# GZ.net
KiCad netlist of a schematic drawn in Altium Designer
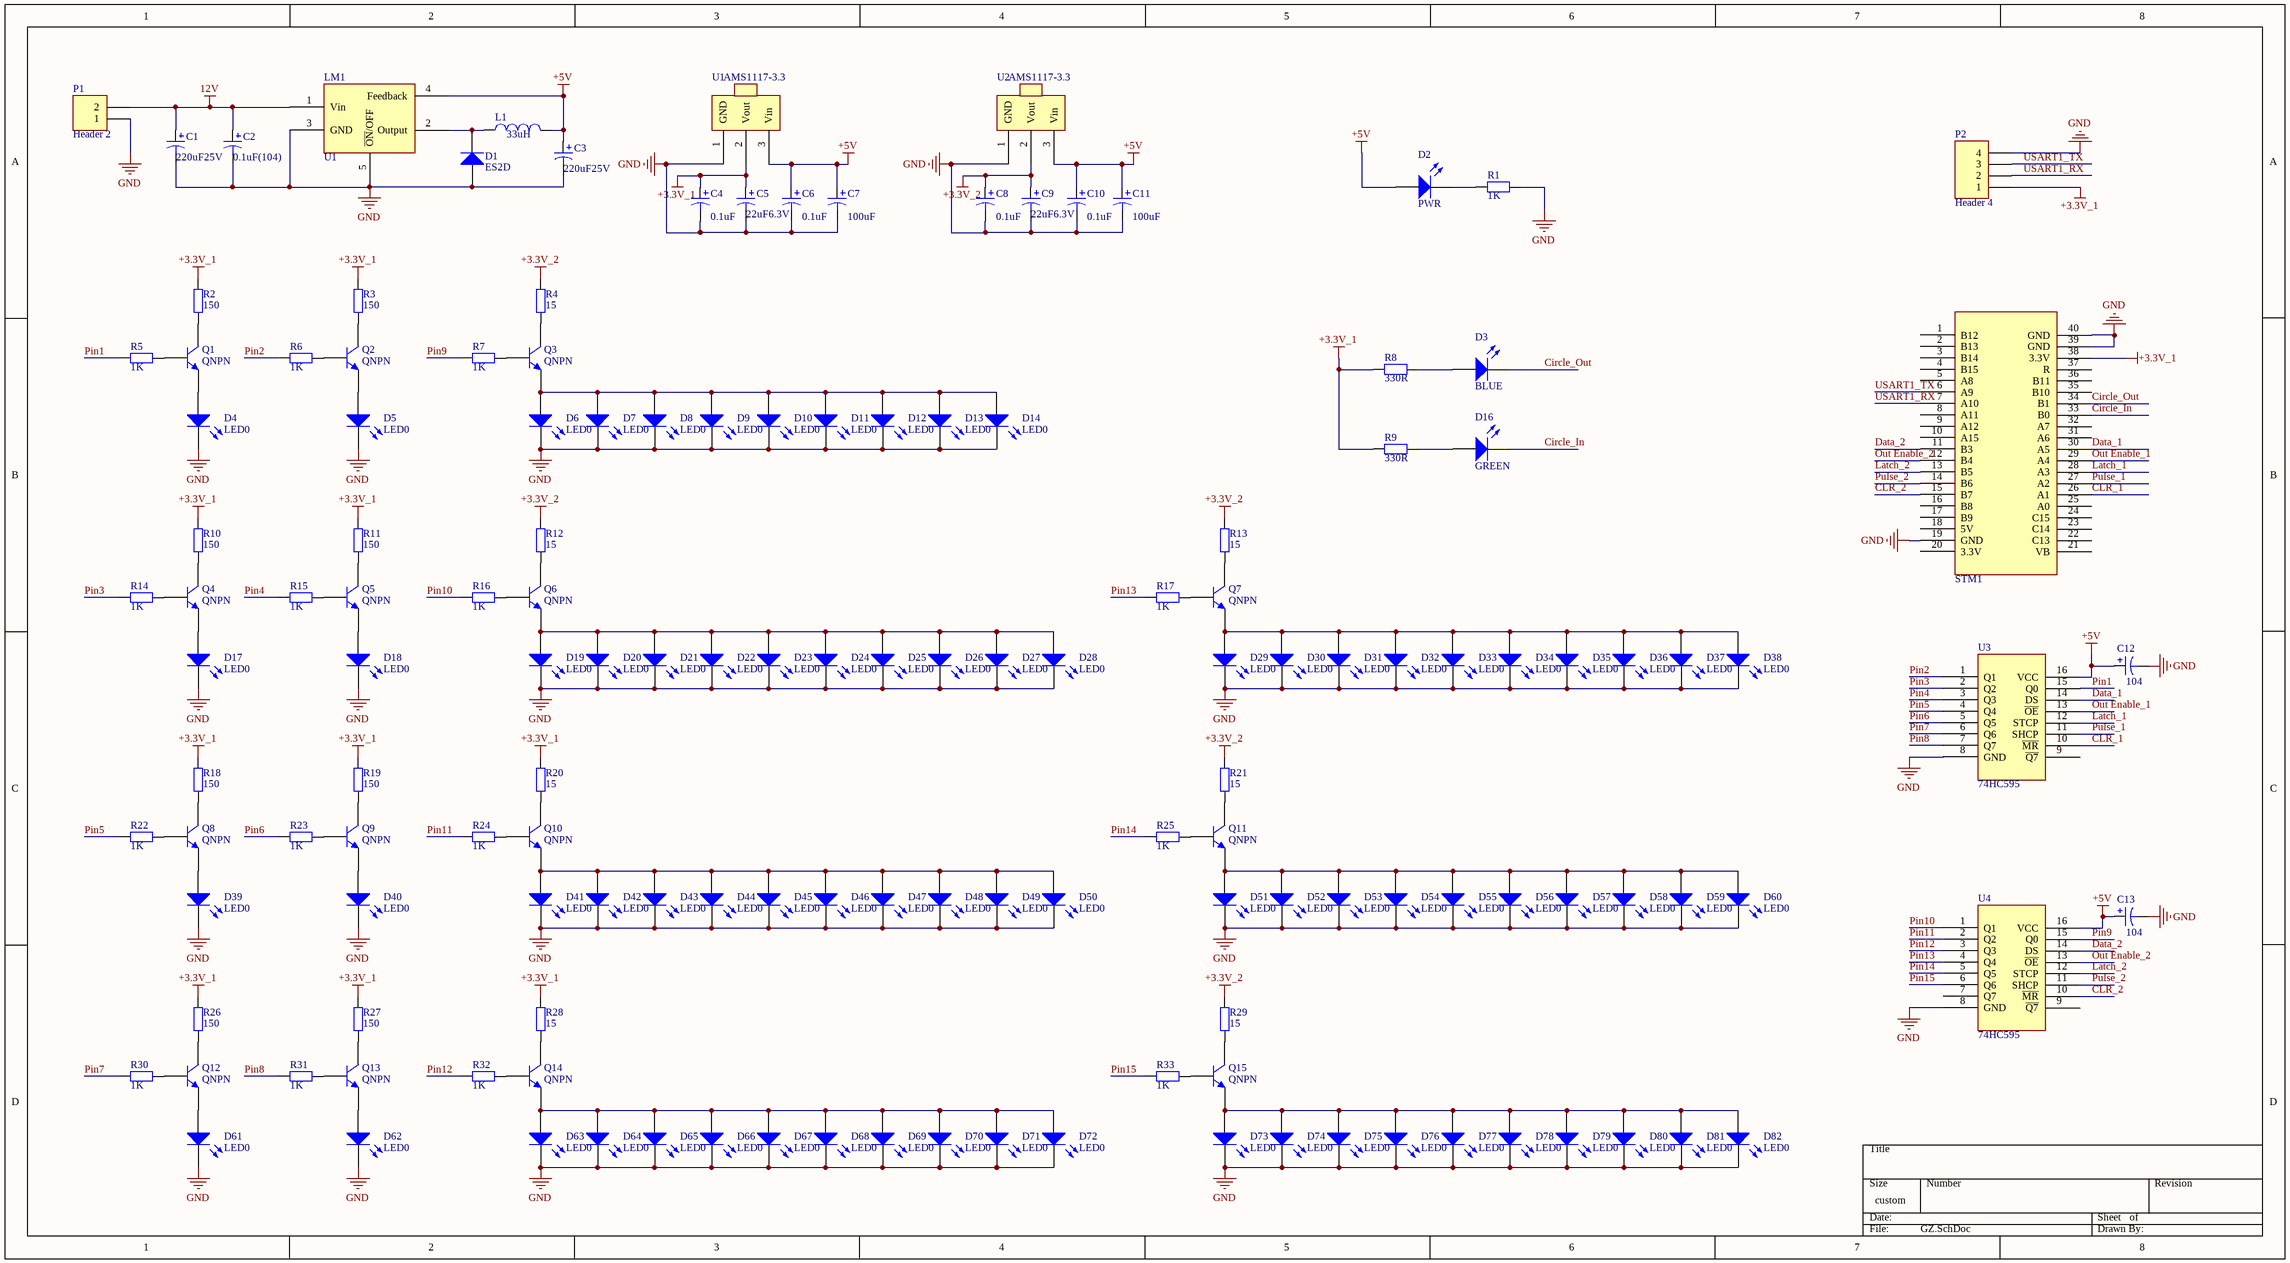
[diagram p0: GZ.SchDoc]

(export (version "E")
  (design (tool "Eeschema 10.0.6"))
  (components
    (comp (ref "C1")
      (value "220uF25V")
      (footprint "3mmcap")
      (description "直插铝电解电容")
      (fields (field (name "PUBLISHER") "Altium Limited"))
      (libsource (lib "Miscellaneous Devices") (part "Cap Pol1"))
    )
    (comp (ref "C2")
      (value "0.1uF(104)")
      (footprint "C0805")
      (description "Polarized Capacitor (Surface Mount)")
      (fields (field (name "PUBLISHER") "Altium Limited"))
      (libsource (lib "Miscellaneous Devices") (part "Cap Pol3"))
    )
    (comp (ref "C3")
      (value "220uF25V")
      (footprint "3mmcap")
      (description "直插铝电解电容")
      (fields (field (name "PUBLISHER") "Altium Limited"))
      (libsource (lib "Miscellaneous Devices") (part "Cap Pol1"))
    )
    (comp (ref "C4")
      (value "0.1uF")
      (footprint "C0805")
      (description "Polarized Capacitor (Surface Mount)")
      (fields (field (name "Comment") "0.1uF(104)") (field (name "PUBLISHER") "Altium Limited"))
      (libsource (lib "Miscellaneous Devices") (part "Cap Pol3"))
    )
    (comp (ref "C5")
      (value "22uF6.3V")
      (footprint "C0805")
      (description "Polarized Capacitor (Surface Mount)")
      (fields (field (name "Comment") "100uf(107)") (field (name "PUBLISHER") "Altium Limited"))
      (libsource (lib "Miscellaneous Devices") (part "Cap Pol3"))
    )
    (comp (ref "C6")
      (value "0.1uF")
      (footprint "C0805")
      (description "Polarized Capacitor (Surface Mount)")
      (fields (field (name "Comment") "0.1uF(104)") (field (name "PUBLISHER") "Altium Limited"))
      (libsource (lib "Miscellaneous Devices") (part "Cap Pol3"))
    )
    (comp (ref "C7")
      (value "100uF")
      (footprint "C0805")
      (description "Polarized Capacitor (Surface Mount)")
      (fields (field (name "Comment") "100uf(107)") (field (name "PUBLISHER") "Altium Limited"))
      (libsource (lib "Miscellaneous Devices") (part "Cap Pol3"))
    )
    (comp (ref "C8")
      (value "0.1uF")
      (footprint "C0805")
      (description "Polarized Capacitor (Surface Mount)")
      (fields (field (name "Comment") "0.1uF(104)") (field (name "PUBLISHER") "Altium Limited"))
      (libsource (lib "Miscellaneous Devices") (part "Cap Pol3"))
    )
    (comp (ref "C9")
      (value "22uF6.3V")
      (footprint "C0805")
      (description "Polarized Capacitor (Surface Mount)")
      (fields (field (name "Comment") "100uf(107)") (field (name "PUBLISHER") "Altium Limited"))
      (libsource (lib "Miscellaneous Devices") (part "Cap Pol3"))
    )
    (comp (ref "C10")
      (value "0.1uF")
      (footprint "C0805")
      (description "Polarized Capacitor (Surface Mount)")
      (fields (field (name "Comment") "0.1uF(104)") (field (name "PUBLISHER") "Altium Limited"))
      (libsource (lib "Miscellaneous Devices") (part "Cap Pol3"))
    )
    (comp (ref "C11")
      (value "100uF")
      (footprint "C0805")
      (description "Polarized Capacitor (Surface Mount)")
      (fields (field (name "Comment") "100uf(107)") (field (name "PUBLISHER") "Altium Limited"))
      (libsource (lib "Miscellaneous Devices") (part "Cap Pol3"))
    )
    (comp (ref "C12")
      (value "104")
      (footprint "C0805")
      (description "Polarized Capacitor (Surface Mount)")
      (fields (field (name "Comment") "0.1uF(104)") (field (name "PUBLISHER") "Altium Limited"))
      (libsource (lib "Miscellaneous Devices") (part "Cap Pol3"))
    )
    (comp (ref "C13")
      (value "104")
      (footprint "C0805")
      (description "Polarized Capacitor (Surface Mount)")
      (fields (field (name "Comment") "0.1uF(104)") (field (name "PUBLISHER") "Altium Limited"))
      (libsource (lib "Miscellaneous Devices") (part "Cap Pol3"))
    )
    (comp (ref "D1")
      (value "ES2D")
      (footprint "SMC")
      (description "Diode")
      (fields (field (name "PUBLISHER") "Altium Limited"))
      (libsource (lib "Miscellaneous Devices") (part "Diode"))
    )
    (comp (ref "D2")
      (value "PWR")
      (footprint "3mm")
      (description "RED-LED")
      (fields (field (name "PUBLISHER") "Altium Limited"))
      (libsource (lib "Miscellaneous Devices") (part "LED0"))
    )
    (comp (ref "D3")
      (value "BLUE")
      (footprint "3mm")
      (description "BLUE-LED")
      (fields (field (name "PUBLISHER") "Altium Limited"))
      (libsource (lib "Miscellaneous Devices") (part "LED0"))
    )
    (comp (ref "D4")
      (value "LED0")
      (footprint "5mm")
      (description "850nm IR-LED")
      (fields (field (name "PUBLISHER") "Altium Limited"))
      (libsource (lib "Miscellaneous Devices") (part "LED0"))
    )
    (comp (ref "D5")
      (value "LED0")
      (footprint "5mm")
      (description "850nm IR-LED")
      (fields (field (name "PUBLISHER") "Altium Limited"))
      (libsource (lib "Miscellaneous Devices") (part "LED0"))
    )
    (comp (ref "D6")
      (value "LED0")
      (footprint "5mm")
      (description "850nm IR-LED")
      (fields (field (name "PUBLISHER") "Altium Limited"))
      (libsource (lib "Miscellaneous Devices") (part "LED0"))
    )
    (comp (ref "D7")
      (value "LED0")
      (footprint "5mm")
      (description "850nm IR-LED")
      (fields (field (name "PUBLISHER") "Altium Limited"))
      (libsource (lib "Miscellaneous Devices") (part "LED0"))
    )
    (comp (ref "D8")
      (value "LED0")
      (footprint "5mm")
      (description "850nm IR-LED")
      (fields (field (name "PUBLISHER") "Altium Limited"))
      (libsource (lib "Miscellaneous Devices") (part "LED0"))
    )
    (comp (ref "D9")
      (value "LED0")
      (footprint "5mm")
      (description "850nm IR-LED")
      (fields (field (name "PUBLISHER") "Altium Limited"))
      (libsource (lib "Miscellaneous Devices") (part "LED0"))
    )
    (comp (ref "D10")
      (value "LED0")
      (footprint "5mm")
      (description "850nm IR-LED")
      (fields (field (name "PUBLISHER") "Altium Limited"))
      (libsource (lib "Miscellaneous Devices") (part "LED0"))
    )
    (comp (ref "D11")
      (value "LED0")
      (footprint "5mm")
      (description "850nm IR-LED")
      (fields (field (name "PUBLISHER") "Altium Limited"))
      (libsource (lib "Miscellaneous Devices") (part "LED0"))
    )
    (comp (ref "D12")
      (value "LED0")
      (footprint "5mm")
      (description "850nm IR-LED")
      (fields (field (name "PUBLISHER") "Altium Limited"))
      (libsource (lib "Miscellaneous Devices") (part "LED0"))
    )
    (comp (ref "D13")
      (value "LED0")
      (footprint "5mm")
      (description "850nm IR-LED")
      (fields (field (name "PUBLISHER") "Altium Limited"))
      (libsource (lib "Miscellaneous Devices") (part "LED0"))
    )
    (comp (ref "D14")
      (value "LED0")
      (footprint "5mm")
      (description "850nm IR-LED")
      (fields (field (name "PUBLISHER") "Altium Limited"))
      (libsource (lib "Miscellaneous Devices") (part "LED0"))
    )
    (comp (ref "D16")
      (value "GREEN")
      (footprint "3mm")
      (description "GREEN-LED")
      (fields (field (name "PUBLISHER") "Altium Limited"))
      (libsource (lib "Miscellaneous Devices") (part "LED0"))
    )
    (comp (ref "D17")
      (value "LED0")
      (footprint "5mm")
      (description "850nm IR-LED")
      (fields (field (name "PUBLISHER") "Altium Limited"))
      (libsource (lib "Miscellaneous Devices") (part "LED0"))
    )
    (comp (ref "D18")
      (value "LED0")
      (footprint "5mm")
      (description "850nm IR-LED")
      (fields (field (name "PUBLISHER") "Altium Limited"))
      (libsource (lib "Miscellaneous Devices") (part "LED0"))
    )
    (comp (ref "D19")
      (value "LED0")
      (footprint "3mm")
      (description "940nm IR-LED")
      (fields (field (name "PUBLISHER") "Altium Limited"))
      (libsource (lib "Miscellaneous Devices") (part "LED0"))
    )
    (comp (ref "D20")
      (value "LED0")
      (footprint "3mm")
      (description "940nm IR-LED")
      (fields (field (name "PUBLISHER") "Altium Limited"))
      (libsource (lib "Miscellaneous Devices") (part "LED0"))
    )
    (comp (ref "D21")
      (value "LED0")
      (footprint "3mm")
      (description "940nm IR-LED")
      (fields (field (name "PUBLISHER") "Altium Limited"))
      (libsource (lib "Miscellaneous Devices") (part "LED0"))
    )
    (comp (ref "D22")
      (value "LED0")
      (footprint "3mm")
      (description "940nm IR-LED")
      (fields (field (name "PUBLISHER") "Altium Limited"))
      (libsource (lib "Miscellaneous Devices") (part "LED0"))
    )
    (comp (ref "D23")
      (value "LED0")
      (footprint "3mm")
      (description "940nm IR-LED")
      (fields (field (name "PUBLISHER") "Altium Limited"))
      (libsource (lib "Miscellaneous Devices") (part "LED0"))
    )
    (comp (ref "D24")
      (value "LED0")
      (footprint "3mm")
      (description "940nm IR-LED")
      (fields (field (name "PUBLISHER") "Altium Limited"))
      (libsource (lib "Miscellaneous Devices") (part "LED0"))
    )
    (comp (ref "D25")
      (value "LED0")
      (footprint "3mm")
      (description "940nm IR-LED")
      (fields (field (name "PUBLISHER") "Altium Limited"))
      (libsource (lib "Miscellaneous Devices") (part "LED0"))
    )
    (comp (ref "D26")
      (value "LED0")
      (footprint "3mm")
      (description "940nm IR-LED")
      (fields (field (name "PUBLISHER") "Altium Limited"))
      (libsource (lib "Miscellaneous Devices") (part "LED0"))
    )
    (comp (ref "D27")
      (value "LED0")
      (footprint "3mm")
      (description "940nm IR-LED")
      (fields (field (name "PUBLISHER") "Altium Limited"))
      (libsource (lib "Miscellaneous Devices") (part "LED0"))
    )
    (comp (ref "D28")
      (value "LED0")
      (footprint "3mm")
      (description "940nm IR-LED")
      (fields (field (name "PUBLISHER") "Altium Limited"))
      (libsource (lib "Miscellaneous Devices") (part "LED0"))
    )
    (comp (ref "D29")
      (value "LED0")
      (footprint "3mm")
      (description "940nm IR-LED")
      (fields (field (name "PUBLISHER") "Altium Limited"))
      (libsource (lib "Miscellaneous Devices") (part "LED0"))
    )
    (comp (ref "D30")
      (value "LED0")
      (footprint "3mm")
      (description "940nm IR-LED")
      (fields (field (name "PUBLISHER") "Altium Limited"))
      (libsource (lib "Miscellaneous Devices") (part "LED0"))
    )
    (comp (ref "D31")
      (value "LED0")
      (footprint "3mm")
      (description "940nm IR-LED")
      (fields (field (name "PUBLISHER") "Altium Limited"))
      (libsource (lib "Miscellaneous Devices") (part "LED0"))
    )
    (comp (ref "D32")
      (value "LED0")
      (footprint "3mm")
      (description "940nm IR-LED")
      (fields (field (name "PUBLISHER") "Altium Limited"))
      (libsource (lib "Miscellaneous Devices") (part "LED0"))
    )
    (comp (ref "D33")
      (value "LED0")
      (footprint "3mm")
      (description "940nm IR-LED")
      (fields (field (name "PUBLISHER") "Altium Limited"))
      (libsource (lib "Miscellaneous Devices") (part "LED0"))
    )
    (comp (ref "D34")
      (value "LED0")
      (footprint "3mm")
      (description "940nm IR-LED")
      (fields (field (name "PUBLISHER") "Altium Limited"))
      (libsource (lib "Miscellaneous Devices") (part "LED0"))
    )
    (comp (ref "D35")
      (value "LED0")
      (footprint "3mm")
      (description "940nm IR-LED")
      (fields (field (name "PUBLISHER") "Altium Limited"))
      (libsource (lib "Miscellaneous Devices") (part "LED0"))
    )
    (comp (ref "D36")
      (value "LED0")
      (footprint "3mm")
      (description "940nm IR-LED")
      (fields (field (name "PUBLISHER") "Altium Limited"))
      (libsource (lib "Miscellaneous Devices") (part "LED0"))
    )
    (comp (ref "D37")
      (value "LED0")
      (footprint "3mm")
      (description "940nm IR-LED")
      (fields (field (name "PUBLISHER") "Altium Limited"))
      (libsource (lib "Miscellaneous Devices") (part "LED0"))
    )
    (comp (ref "D38")
      (value "LED0")
      (footprint "3mm")
      (description "940nm IR-LED")
      (fields (field (name "PUBLISHER") "Altium Limited"))
      (libsource (lib "Miscellaneous Devices") (part "LED0"))
    )
    (comp (ref "D39")
      (value "LED0")
      (footprint "3mm")
      (description "940nm IR-LED")
      (fields (field (name "PUBLISHER") "Altium Limited"))
      (libsource (lib "Miscellaneous Devices") (part "LED0"))
    )
    (comp (ref "D40")
      (value "LED0")
      (footprint "3mm")
      (description "940nm IR-LED")
      (fields (field (name "PUBLISHER") "Altium Limited"))
      (libsource (lib "Miscellaneous Devices") (part "LED0"))
    )
    (comp (ref "D41")
      (value "LED0")
      (footprint "3mm")
      (description "940nm IR-LED")
      (fields (field (name "PUBLISHER") "Altium Limited"))
      (libsource (lib "Miscellaneous Devices") (part "LED0"))
    )
    (comp (ref "D42")
      (value "LED0")
      (footprint "3mm")
      (description "940nm IR-LED")
      (fields (field (name "PUBLISHER") "Altium Limited"))
      (libsource (lib "Miscellaneous Devices") (part "LED0"))
    )
    (comp (ref "D43")
      (value "LED0")
      (footprint "3mm")
      (description "940nm IR-LED")
      (fields (field (name "PUBLISHER") "Altium Limited"))
      (libsource (lib "Miscellaneous Devices") (part "LED0"))
    )
    (comp (ref "D44")
      (value "LED0")
      (footprint "3mm")
      (description "940nm IR-LED")
      (fields (field (name "PUBLISHER") "Altium Limited"))
      (libsource (lib "Miscellaneous Devices") (part "LED0"))
    )
    (comp (ref "D45")
      (value "LED0")
      (footprint "3mm")
      (description "940nm IR-LED")
      (fields (field (name "PUBLISHER") "Altium Limited"))
      (libsource (lib "Miscellaneous Devices") (part "LED0"))
    )
    (comp (ref "D46")
      (value "LED0")
      (footprint "3mm")
      (description "940nm IR-LED")
      (fields (field (name "PUBLISHER") "Altium Limited"))
      (libsource (lib "Miscellaneous Devices") (part "LED0"))
    )
    (comp (ref "D47")
      (value "LED0")
      (footprint "3mm")
      (description "940nm IR-LED")
      (fields (field (name "PUBLISHER") "Altium Limited"))
      (libsource (lib "Miscellaneous Devices") (part "LED0"))
    )
    (comp (ref "D48")
      (value "LED0")
      (footprint "3mm")
      (description "940nm IR-LED")
      (fields (field (name "PUBLISHER") "Altium Limited"))
      (libsource (lib "Miscellaneous Devices") (part "LED0"))
    )
    (comp (ref "D49")
      (value "LED0")
      (footprint "3mm")
      (description "940nm IR-LED")
      (fields (field (name "PUBLISHER") "Altium Limited"))
      (libsource (lib "Miscellaneous Devices") (part "LED0"))
    )
    (comp (ref "D50")
      (value "LED0")
      (footprint "3mm")
      (description "940nm IR-LED")
      (fields (field (name "PUBLISHER") "Altium Limited"))
      (libsource (lib "Miscellaneous Devices") (part "LED0"))
    )
    (comp (ref "D51")
      (value "LED0")
      (footprint "3mm")
      (description "940nm IR-LED")
      (fields (field (name "PUBLISHER") "Altium Limited"))
      (libsource (lib "Miscellaneous Devices") (part "LED0"))
    )
    (comp (ref "D52")
      (value "LED0")
      (footprint "3mm")
      (description "940nm IR-LED")
      (fields (field (name "PUBLISHER") "Altium Limited"))
      (libsource (lib "Miscellaneous Devices") (part "LED0"))
    )
    (comp (ref "D53")
      (value "LED0")
      (footprint "3mm")
      (description "940nm IR-LED")
      (fields (field (name "PUBLISHER") "Altium Limited"))
      (libsource (lib "Miscellaneous Devices") (part "LED0"))
    )
    (comp (ref "D54")
      (value "LED0")
      (footprint "3mm")
      (description "940nm IR-LED")
      (fields (field (name "PUBLISHER") "Altium Limited"))
      (libsource (lib "Miscellaneous Devices") (part "LED0"))
    )
    (comp (ref "D55")
      (value "LED0")
      (footprint "3mm")
      (description "940nm IR-LED")
      (fields (field (name "PUBLISHER") "Altium Limited"))
      (libsource (lib "Miscellaneous Devices") (part "LED0"))
    )
    (comp (ref "D56")
      (value "LED0")
      (footprint "3mm")
      (description "940nm IR-LED")
      (fields (field (name "PUBLISHER") "Altium Limited"))
      (libsource (lib "Miscellaneous Devices") (part "LED0"))
    )
    (comp (ref "D57")
      (value "LED0")
      (footprint "3mm")
      (description "940nm IR-LED")
      (fields (field (name "PUBLISHER") "Altium Limited"))
      (libsource (lib "Miscellaneous Devices") (part "LED0"))
    )
    (comp (ref "D58")
      (value "LED0")
      (footprint "3mm")
      (description "940nm IR-LED")
      (fields (field (name "PUBLISHER") "Altium Limited"))
      (libsource (lib "Miscellaneous Devices") (part "LED0"))
    )
    (comp (ref "D59")
      (value "LED0")
      (footprint "3mm")
      (description "940nm IR-LED")
      (fields (field (name "PUBLISHER") "Altium Limited"))
      (libsource (lib "Miscellaneous Devices") (part "LED0"))
    )
    (comp (ref "D60")
      (value "LED0")
      (footprint "3mm")
      (description "940nm IR-LED")
      (fields (field (name "PUBLISHER") "Altium Limited"))
      (libsource (lib "Miscellaneous Devices") (part "LED0"))
    )
    (comp (ref "D61")
      (value "LED0")
      (footprint "3mm")
      (description "940nm IR-LED")
      (fields (field (name "PUBLISHER") "Altium Limited"))
      (libsource (lib "Miscellaneous Devices") (part "LED0"))
    )
    (comp (ref "D62")
      (value "LED0")
      (footprint "3mm")
      (description "940nm IR-LED")
      (fields (field (name "PUBLISHER") "Altium Limited"))
      (libsource (lib "Miscellaneous Devices") (part "LED0"))
    )
    (comp (ref "D63")
      (value "LED0")
      (footprint "3mm")
      (description "940nm IR-LED")
      (fields (field (name "PUBLISHER") "Altium Limited"))
      (libsource (lib "Miscellaneous Devices") (part "LED0"))
    )
    (comp (ref "D64")
      (value "LED0")
      (footprint "3mm")
      (description "940nm IR-LED")
      (fields (field (name "PUBLISHER") "Altium Limited"))
      (libsource (lib "Miscellaneous Devices") (part "LED0"))
    )
    (comp (ref "D65")
      (value "LED0")
      (footprint "3mm")
      (description "940nm IR-LED")
      (fields (field (name "PUBLISHER") "Altium Limited"))
      (libsource (lib "Miscellaneous Devices") (part "LED0"))
    )
    (comp (ref "D66")
      (value "LED0")
      (footprint "3mm")
      (description "940nm IR-LED")
      (fields (field (name "PUBLISHER") "Altium Limited"))
      (libsource (lib "Miscellaneous Devices") (part "LED0"))
    )
    (comp (ref "D67")
      (value "LED0")
      (footprint "3mm")
      (description "940nm IR-LED")
      (fields (field (name "PUBLISHER") "Altium Limited"))
      (libsource (lib "Miscellaneous Devices") (part "LED0"))
    )
    (comp (ref "D68")
      (value "LED0")
      (footprint "3mm")
      (description "940nm IR-LED")
      (fields (field (name "PUBLISHER") "Altium Limited"))
      (libsource (lib "Miscellaneous Devices") (part "LED0"))
    )
    (comp (ref "D69")
      (value "LED0")
      (footprint "3mm")
      (description "940nm IR-LED")
      (fields (field (name "PUBLISHER") "Altium Limited"))
      (libsource (lib "Miscellaneous Devices") (part "LED0"))
    )
    (comp (ref "D70")
      (value "LED0")
      (footprint "3mm")
      (description "940nm IR-LED")
      (fields (field (name "PUBLISHER") "Altium Limited"))
      (libsource (lib "Miscellaneous Devices") (part "LED0"))
    )
    (comp (ref "D71")
      (value "LED0")
      (footprint "3mm")
      (description "940nm IR-LED")
      (fields (field (name "PUBLISHER") "Altium Limited"))
      (libsource (lib "Miscellaneous Devices") (part "LED0"))
    )
    (comp (ref "D72")
      (value "LED0")
      (footprint "3mm")
      (description "940nm IR-LED")
      (fields (field (name "PUBLISHER") "Altium Limited"))
      (libsource (lib "Miscellaneous Devices") (part "LED0"))
    )
    (comp (ref "D73")
      (value "LED0")
      (footprint "3mm")
      (description "940nm IR-LED")
      (fields (field (name "PUBLISHER") "Altium Limited"))
      (libsource (lib "Miscellaneous Devices") (part "LED0"))
    )
    (comp (ref "D74")
      (value "LED0")
      (footprint "3mm")
      (description "940nm IR-LED")
      (fields (field (name "PUBLISHER") "Altium Limited"))
      (libsource (lib "Miscellaneous Devices") (part "LED0"))
    )
    (comp (ref "D75")
      (value "LED0")
      (footprint "3mm")
      (description "940nm IR-LED")
      (fields (field (name "PUBLISHER") "Altium Limited"))
      (libsource (lib "Miscellaneous Devices") (part "LED0"))
    )
    (comp (ref "D76")
      (value "LED0")
      (footprint "3mm")
      (description "940nm IR-LED")
      (fields (field (name "PUBLISHER") "Altium Limited"))
      (libsource (lib "Miscellaneous Devices") (part "LED0"))
    )
    (comp (ref "D77")
      (value "LED0")
      (footprint "3mm")
      (description "940nm IR-LED")
      (fields (field (name "PUBLISHER") "Altium Limited"))
      (libsource (lib "Miscellaneous Devices") (part "LED0"))
    )
    (comp (ref "D78")
      (value "LED0")
      (footprint "3mm")
      (description "940nm IR-LED")
      (fields (field (name "PUBLISHER") "Altium Limited"))
      (libsource (lib "Miscellaneous Devices") (part "LED0"))
    )
    (comp (ref "D79")
      (value "LED0")
      (footprint "3mm")
      (description "940nm IR-LED")
      (fields (field (name "PUBLISHER") "Altium Limited"))
      (libsource (lib "Miscellaneous Devices") (part "LED0"))
    )
    (comp (ref "D80")
      (value "LED0")
      (footprint "3mm")
      (description "940nm IR-LED")
      (fields (field (name "PUBLISHER") "Altium Limited"))
      (libsource (lib "Miscellaneous Devices") (part "LED0"))
    )
    (comp (ref "D81")
      (value "LED0")
      (footprint "3mm")
      (description "940nm IR-LED")
      (fields (field (name "PUBLISHER") "Altium Limited"))
      (libsource (lib "Miscellaneous Devices") (part "LED0"))
    )
    (comp (ref "D82")
      (value "LED0")
      (footprint "3mm")
      (description "940nm IR-LED")
      (fields (field (name "PUBLISHER") "Altium Limited"))
      (libsource (lib "Miscellaneous Devices") (part "LED0"))
    )
    (comp (ref "L1")
      (value "33uH")
      (footprint "7*7mm贴片电感")
      (fields (field (name "Comment") "Inductor") (field (name "PUBLISHER") "Altium Limited"))
      (libsource (lib "Miscellaneous Devices") (part "Inductor"))
    )
    (comp (ref "LM1")
      (value "U1")
      (footprint "TO-263-5")
      (description "LM2596-5.0")
      (libsource (lib "PPSchlib") (part "LM2596"))
    )
    (comp (ref "P1")
      (value "Header 2")
      (footprint "HDR1X2")
      (description "电源接口")
      (fields (field (name "PUBLISHER") "Altium Limited"))
      (libsource (lib "Miscellaneous Connectors") (part "Header 2"))
    )
    (comp (ref "P2")
      (value "Header 4")
      (footprint "HDR1X4")
      (description "串口接口")
      (fields (field (name "PUBLISHER") "Altium Limited"))
      (libsource (lib "Miscellaneous Connectors") (part "Header 4"))
    )
    (comp (ref "Q1")
      (value "QNPN")
      (footprint "SOT-23B_N")
      (description "NPN Bipolar Transistor")
      (fields (field (name "PUBLISHER") "Altium Limited"))
      (libsource (lib "Miscellaneous Devices") (part "QNPN"))
    )
    (comp (ref "Q2")
      (value "QNPN")
      (footprint "SOT-23B_N")
      (description "NPN Bipolar Transistor")
      (fields (field (name "PUBLISHER") "Altium Limited"))
      (libsource (lib "Miscellaneous Devices") (part "QNPN"))
    )
    (comp (ref "Q3")
      (value "QNPN")
      (footprint "SOT-23B_N")
      (description "NPN Bipolar Transistor")
      (fields (field (name "PUBLISHER") "Altium Limited"))
      (libsource (lib "Miscellaneous Devices") (part "QNPN"))
    )
    (comp (ref "Q4")
      (value "QNPN")
      (footprint "SOT-23B_N")
      (description "NPN Bipolar Transistor")
      (fields (field (name "PUBLISHER") "Altium Limited"))
      (libsource (lib "Miscellaneous Devices") (part "QNPN"))
    )
    (comp (ref "Q5")
      (value "QNPN")
      (footprint "SOT-23B_N")
      (description "NPN Bipolar Transistor")
      (fields (field (name "PUBLISHER") "Altium Limited"))
      (libsource (lib "Miscellaneous Devices") (part "QNPN"))
    )
    (comp (ref "Q6")
      (value "QNPN")
      (footprint "SOT-23B_N")
      (description "NPN Bipolar Transistor")
      (fields (field (name "PUBLISHER") "Altium Limited"))
      (libsource (lib "Miscellaneous Devices") (part "QNPN"))
    )
    (comp (ref "Q7")
      (value "QNPN")
      (footprint "SOT-23B_N")
      (description "NPN Bipolar Transistor")
      (fields (field (name "PUBLISHER") "Altium Limited"))
      (libsource (lib "Miscellaneous Devices") (part "QNPN"))
    )
    (comp (ref "Q8")
      (value "QNPN")
      (footprint "SOT-23B_N")
      (description "NPN Bipolar Transistor")
      (fields (field (name "PUBLISHER") "Altium Limited"))
      (libsource (lib "Miscellaneous Devices") (part "QNPN"))
    )
    (comp (ref "Q9")
      (value "QNPN")
      (footprint "SOT-23B_N")
      (description "NPN Bipolar Transistor")
      (fields (field (name "PUBLISHER") "Altium Limited"))
      (libsource (lib "Miscellaneous Devices") (part "QNPN"))
    )
    (comp (ref "Q10")
      (value "QNPN")
      (footprint "SOT-23B_N")
      (description "NPN Bipolar Transistor")
      (fields (field (name "PUBLISHER") "Altium Limited"))
      (libsource (lib "Miscellaneous Devices") (part "QNPN"))
    )
    (comp (ref "Q11")
      (value "QNPN")
      (footprint "SOT-23B_N")
      (description "NPN Bipolar Transistor")
      (fields (field (name "PUBLISHER") "Altium Limited"))
      (libsource (lib "Miscellaneous Devices") (part "QNPN"))
    )
    (comp (ref "Q12")
      (value "QNPN")
      (footprint "SOT-23B_N")
      (description "NPN Bipolar Transistor")
      (fields (field (name "PUBLISHER") "Altium Limited"))
      (libsource (lib "Miscellaneous Devices") (part "QNPN"))
    )
    (comp (ref "Q13")
      (value "QNPN")
      (footprint "SOT-23B_N")
      (description "NPN Bipolar Transistor")
      (fields (field (name "PUBLISHER") "Altium Limited"))
      (libsource (lib "Miscellaneous Devices") (part "QNPN"))
    )
    (comp (ref "Q14")
      (value "QNPN")
      (footprint "SOT-23B_N")
      (description "NPN Bipolar Transistor")
      (fields (field (name "PUBLISHER") "Altium Limited"))
      (libsource (lib "Miscellaneous Devices") (part "QNPN"))
    )
    (comp (ref "Q15")
      (value "QNPN")
      (footprint "SOT-23B_N")
      (description "NPN Bipolar Transistor")
      (fields (field (name "PUBLISHER") "Altium Limited"))
      (libsource (lib "Miscellaneous Devices") (part "QNPN"))
    )
    (comp (ref "R1")
      (value "1K")
      (footprint "6-0805_N")
      (description "Resistor")
      (fields (field (name "Comment") "Res2") (field (name "PUBLISHER") "Altium Limited"))
      (libsource (lib "") (part "Res2_1"))
    )
    (comp (ref "R2")
      (value "150")
      (footprint "6-0805_N")
      (description "Resistor")
      (fields (field (name "Comment") "Res2") (field (name "PUBLISHER") "Altium Limited"))
      (libsource (lib "Miscellaneous Devices") (part "Res2"))
    )
    (comp (ref "R3")
      (value "150")
      (footprint "6-0805_N")
      (description "Resistor")
      (fields (field (name "Comment") "Res2") (field (name "PUBLISHER") "Altium Limited"))
      (libsource (lib "Miscellaneous Devices") (part "Res2"))
    )
    (comp (ref "R4")
      (value "15")
      (footprint "6-0805_N")
      (description "Resistor")
      (fields (field (name "Comment") "Res2") (field (name "PUBLISHER") "Altium Limited"))
      (libsource (lib "Miscellaneous Devices") (part "Res2"))
    )
    (comp (ref "R5")
      (value "1K")
      (footprint "6-0805_N")
      (description "Resistor")
      (fields (field (name "Comment") "Res2") (field (name "PUBLISHER") "Altium Limited"))
      (libsource (lib "") (part "Res2_1"))
    )
    (comp (ref "R6")
      (value "1K")
      (footprint "6-0805_N")
      (description "Resistor")
      (fields (field (name "Comment") "Res2") (field (name "PUBLISHER") "Altium Limited"))
      (libsource (lib "") (part "Res2_1"))
    )
    (comp (ref "R7")
      (value "1K")
      (footprint "6-0805_N")
      (description "Resistor")
      (fields (field (name "Comment") "Res2") (field (name "PUBLISHER") "Altium Limited"))
      (libsource (lib "") (part "Res2_1"))
    )
    (comp (ref "R8")
      (value "330R")
      (footprint "6-0805_N")
      (description "Resistor")
      (fields (field (name "Comment") "Res2") (field (name "PUBLISHER") "Altium Limited"))
      (libsource (lib "") (part "Res2_1"))
    )
    (comp (ref "R9")
      (value "330R")
      (footprint "6-0805_N")
      (description "Resistor")
      (fields (field (name "Comment") "Res2") (field (name "PUBLISHER") "Altium Limited"))
      (libsource (lib "") (part "Res2_1"))
    )
    (comp (ref "R10")
      (value "150")
      (footprint "6-0805_N")
      (description "Resistor")
      (fields (field (name "Comment") "Res2") (field (name "PUBLISHER") "Altium Limited"))
      (libsource (lib "Miscellaneous Devices") (part "Res2"))
    )
    (comp (ref "R11")
      (value "150")
      (footprint "6-0805_N")
      (description "Resistor")
      (fields (field (name "Comment") "Res2") (field (name "PUBLISHER") "Altium Limited"))
      (libsource (lib "Miscellaneous Devices") (part "Res2"))
    )
    (comp (ref "R12")
      (value "15")
      (footprint "6-0805_N")
      (description "Resistor")
      (fields (field (name "Comment") "Res2") (field (name "PUBLISHER") "Altium Limited"))
      (libsource (lib "Miscellaneous Devices") (part "Res2"))
    )
    (comp (ref "R13")
      (value "15")
      (footprint "6-0805_N")
      (description "Resistor")
      (fields (field (name "Comment") "Res2") (field (name "PUBLISHER") "Altium Limited"))
      (libsource (lib "Miscellaneous Devices") (part "Res2"))
    )
    (comp (ref "R14")
      (value "1K")
      (footprint "6-0805_N")
      (description "Resistor")
      (fields (field (name "Comment") "Res2") (field (name "PUBLISHER") "Altium Limited"))
      (libsource (lib "") (part "Res2_1"))
    )
    (comp (ref "R15")
      (value "1K")
      (footprint "6-0805_N")
      (description "Resistor")
      (fields (field (name "Comment") "Res2") (field (name "PUBLISHER") "Altium Limited"))
      (libsource (lib "") (part "Res2_1"))
    )
    (comp (ref "R16")
      (value "1K")
      (footprint "6-0805_N")
      (description "Resistor")
      (fields (field (name "Comment") "Res2") (field (name "PUBLISHER") "Altium Limited"))
      (libsource (lib "") (part "Res2_1"))
    )
    (comp (ref "R17")
      (value "1K")
      (footprint "6-0805_N")
      (description "Resistor")
      (fields (field (name "Comment") "Res2") (field (name "PUBLISHER") "Altium Limited"))
      (libsource (lib "") (part "Res2_1"))
    )
    (comp (ref "R18")
      (value "150")
      (footprint "6-0805_N")
      (description "Resistor")
      (fields (field (name "Comment") "Res2") (field (name "PUBLISHER") "Altium Limited"))
      (libsource (lib "Miscellaneous Devices") (part "Res2"))
    )
    (comp (ref "R19")
      (value "150")
      (footprint "6-0805_N")
      (description "Resistor")
      (fields (field (name "Comment") "Res2") (field (name "PUBLISHER") "Altium Limited"))
      (libsource (lib "Miscellaneous Devices") (part "Res2"))
    )
    (comp (ref "R20")
      (value "15")
      (footprint "6-0805_N")
      (description "Resistor")
      (fields (field (name "Comment") "Res2") (field (name "PUBLISHER") "Altium Limited"))
      (libsource (lib "Miscellaneous Devices") (part "Res2"))
    )
    (comp (ref "R21")
      (value "15")
      (footprint "6-0805_N")
      (description "Resistor")
      (fields (field (name "Comment") "Res2") (field (name "PUBLISHER") "Altium Limited"))
      (libsource (lib "Miscellaneous Devices") (part "Res2"))
    )
    (comp (ref "R22")
      (value "1K")
      (footprint "6-0805_N")
      (description "Resistor")
      (fields (field (name "Comment") "Res2") (field (name "PUBLISHER") "Altium Limited"))
      (libsource (lib "") (part "Res2_1"))
    )
    (comp (ref "R23")
      (value "1K")
      (footprint "6-0805_N")
      (description "Resistor")
      (fields (field (name "Comment") "Res2") (field (name "PUBLISHER") "Altium Limited"))
      (libsource (lib "") (part "Res2_1"))
    )
    (comp (ref "R24")
      (value "1K")
      (footprint "6-0805_N")
      (description "Resistor")
      (fields (field (name "Comment") "Res2") (field (name "PUBLISHER") "Altium Limited"))
      (libsource (lib "") (part "Res2_1"))
    )
    (comp (ref "R25")
      (value "1K")
      (footprint "6-0805_N")
      (description "Resistor")
      (fields (field (name "Comment") "Res2") (field (name "PUBLISHER") "Altium Limited"))
      (libsource (lib "") (part "Res2_1"))
    )
    (comp (ref "R26")
      (value "150")
      (footprint "6-0805_N")
      (description "Resistor")
      (fields (field (name "Comment") "Res2") (field (name "PUBLISHER") "Altium Limited"))
      (libsource (lib "Miscellaneous Devices") (part "Res2"))
    )
    (comp (ref "R27")
      (value "150")
      (footprint "6-0805_N")
      (description "Resistor")
      (fields (field (name "Comment") "Res2") (field (name "PUBLISHER") "Altium Limited"))
      (libsource (lib "Miscellaneous Devices") (part "Res2"))
    )
    (comp (ref "R28")
      (value "15")
      (footprint "6-0805_N")
      (description "Resistor")
      (fields (field (name "Comment") "Res2") (field (name "PUBLISHER") "Altium Limited"))
      (libsource (lib "Miscellaneous Devices") (part "Res2"))
    )
    (comp (ref "R29")
      (value "15")
      (footprint "6-0805_N")
      (description "Resistor")
      (fields (field (name "Comment") "Res2") (field (name "PUBLISHER") "Altium Limited"))
      (libsource (lib "Miscellaneous Devices") (part "Res2"))
    )
    (comp (ref "R30")
      (value "1K")
      (footprint "6-0805_N")
      (description "Resistor")
      (fields (field (name "Comment") "Res2") (field (name "PUBLISHER") "Altium Limited"))
      (libsource (lib "") (part "Res2_1"))
    )
    (comp (ref "R31")
      (value "1K")
      (footprint "6-0805_N")
      (description "Resistor")
      (fields (field (name "Comment") "Res2") (field (name "PUBLISHER") "Altium Limited"))
      (libsource (lib "") (part "Res2_1"))
    )
    (comp (ref "R32")
      (value "1K")
      (footprint "6-0805_N")
      (description "Resistor")
      (fields (field (name "Comment") "Res2") (field (name "PUBLISHER") "Altium Limited"))
      (libsource (lib "") (part "Res2_1"))
    )
    (comp (ref "R33")
      (value "1K")
      (footprint "6-0805_N")
      (description "Resistor")
      (fields (field (name "Comment") "Res2") (field (name "PUBLISHER") "Altium Limited"))
      (libsource (lib "") (part "Res2_1"))
    )
    (comp (ref "STM1")
      (value "STM32F103C8核心板")
      (footprint "STM32F103C8T6")
      (libsource (lib "PPSchlib") (part "STM32F103C8核心板"))
    )
    (comp (ref "U1")
      (value "AMS1117-3.3")
      (footprint "SOT223_N")
      (libsource (lib "PPSchlib") (part "AMS1117-3.3"))
    )
    (comp (ref "U2")
      (value "AMS1117-3.3")
      (footprint "SOT223_N")
      (libsource (lib "PPSchlib") (part "AMS1117-3.3"))
    )
    (comp (ref "U3") (value "74HC595") (footprint "dip16") (libsource (lib "PPSchlib") (part "74HC595")))
    (comp (ref "U4") (value "74HC595") (footprint "dip16") (libsource (lib "PPSchlib") (part "74HC595")))
  )
  (nets
    (net (code "1") (name "+3.3V_1") (class "Default")
      (node (ref "C4") (pin "1") (pinfunction "1_1") (pintype "passive"))
      (node (ref "C5") (pin "1") (pinfunction "1_1") (pintype "passive"))
      (node (ref "P2") (pin "1") (pinfunction "1_1") (pintype "passive"))
      (node (ref "R10") (pin "1") (pinfunction "1_1") (pintype "passive"))
      (node (ref "R11") (pin "1") (pinfunction "1_1") (pintype "passive"))
      (node (ref "R18") (pin "1") (pinfunction "1_1") (pintype "passive"))
      (node (ref "R19") (pin "1") (pinfunction "1_1") (pintype "passive"))
      (node (ref "R2") (pin "1") (pinfunction "1_1") (pintype "passive"))
      (node (ref "R20") (pin "1") (pinfunction "1_1") (pintype "passive"))
      (node (ref "R26") (pin "1") (pinfunction "1_1") (pintype "passive"))
      (node (ref "R27") (pin "1") (pinfunction "1_1") (pintype "passive"))
      (node (ref "R28") (pin "1") (pinfunction "1_1") (pintype "passive"))
      (node (ref "R3") (pin "1") (pinfunction "1_1") (pintype "passive"))
      (node (ref "R8") (pin "2") (pinfunction "2_2") (pintype "passive"))
      (node (ref "R9") (pin "2") (pinfunction "2_2") (pintype "passive"))
      (node (ref "STM1") (pin "38") (pinfunction "3.3V_38") (pintype "passive"))
      (node (ref "U1") (pin "2") (pinfunction "Vout_2") (pintype "passive"))
    )
    (net (code "2") (name "+3.3V_2") (class "Default")
      (node (ref "C8") (pin "1") (pinfunction "1_1") (pintype "passive"))
      (node (ref "C9") (pin "1") (pinfunction "1_1") (pintype "passive"))
      (node (ref "R12") (pin "1") (pinfunction "1_1") (pintype "passive"))
      (node (ref "R13") (pin "1") (pinfunction "1_1") (pintype "passive"))
      (node (ref "R21") (pin "1") (pinfunction "1_1") (pintype "passive"))
      (node (ref "R29") (pin "1") (pinfunction "1_1") (pintype "passive"))
      (node (ref "R4") (pin "1") (pinfunction "1_1") (pintype "passive"))
      (node (ref "U2") (pin "2") (pinfunction "Vout_2") (pintype "passive"))
    )
    (net (code "3") (name "+5V") (class "Default")
      (node (ref "C10") (pin "1") (pinfunction "1_1") (pintype "passive"))
      (node (ref "C11") (pin "1") (pinfunction "1_1") (pintype "passive"))
      (node (ref "C12") (pin "1") (pinfunction "1_1") (pintype "passive"))
      (node (ref "C13") (pin "1") (pinfunction "1_1") (pintype "passive"))
      (node (ref "C3") (pin "1") (pinfunction "1_1") (pintype "passive"))
      (node (ref "C6") (pin "1") (pinfunction "1_1") (pintype "passive"))
      (node (ref "C7") (pin "1") (pinfunction "1_1") (pintype "passive"))
      (node (ref "D2") (pin "1") (pinfunction "A_1") (pintype "passive"))
      (node (ref "L1") (pin "2") (pinfunction "2_2") (pintype "passive"))
      (node (ref "LM1") (pin "4") (pinfunction "Feedback_4") (pintype "passive"))
      (node (ref "U1") (pin "3") (pinfunction "Vin_3") (pintype "passive"))
      (node (ref "U2") (pin "3") (pinfunction "Vin_3") (pintype "passive"))
      (node (ref "U3") (pin "16") (pinfunction "VCC_16") (pintype "passive"))
      (node (ref "U4") (pin "16") (pinfunction "VCC_16") (pintype "passive"))
    )
    (net (code "4") (name "/CLR_1") (class "Default")
      (node (ref "STM1") (pin "26") (pinfunction "A1_26") (pintype "passive"))
      (node (ref "U3") (pin "10") (pinfunction "~{MR}_10") (pintype "passive"))
    )
    (net (code "5") (name "/CLR_2") (class "Default")
      (node (ref "STM1") (pin "15") (pinfunction "B7_15") (pintype "passive"))
      (node (ref "U4") (pin "10") (pinfunction "~{MR}_10") (pintype "passive"))
    )
    (net (code "6") (name "/Circle_In") (class "Default")
      (node (ref "D16") (pin "2") (pinfunction "K_2") (pintype "passive"))
      (node (ref "STM1") (pin "33") (pinfunction "B0_33") (pintype "passive"))
    )
    (net (code "7") (name "/Circle_Out") (class "Default")
      (node (ref "D3") (pin "2") (pinfunction "K_2") (pintype "passive"))
      (node (ref "STM1") (pin "34") (pinfunction "B1_34") (pintype "passive"))
    )
    (net (code "8") (name "/Data_1") (class "Default")
      (node (ref "STM1") (pin "30") (pinfunction "A5_30") (pintype "passive"))
      (node (ref "U3") (pin "14") (pinfunction "DS_14") (pintype "passive"))
    )
    (net (code "9") (name "/Data_2") (class "Default")
      (node (ref "STM1") (pin "11") (pinfunction "B3_11") (pintype "passive"))
      (node (ref "U4") (pin "14") (pinfunction "DS_14") (pintype "passive"))
    )
    (net (code "10") (name "/Latch_1") (class "Default")
      (node (ref "STM1") (pin "28") (pinfunction "A3_28") (pintype "passive"))
      (node (ref "U3") (pin "12") (pinfunction "STCP_12") (pintype "passive"))
    )
    (net (code "11") (name "/Latch_2") (class "Default")
      (node (ref "STM1") (pin "13") (pinfunction "B5_13") (pintype "passive"))
      (node (ref "U4") (pin "12") (pinfunction "STCP_12") (pintype "passive"))
    )
    (net (code "12") (name "/Out Enable_1") (class "Default")
      (node (ref "STM1") (pin "29") (pinfunction "A4_29") (pintype "passive"))
      (node (ref "U3") (pin "13") (pinfunction "~{OE}_13") (pintype "passive"))
    )
    (net (code "13") (name "/Out Enable_2") (class "Default")
      (node (ref "STM1") (pin "12") (pinfunction "B4_12") (pintype "passive"))
      (node (ref "U4") (pin "13") (pinfunction "~{OE}_13") (pintype "passive"))
    )
    (net (code "14") (name "/Pin1") (class "Default")
      (node (ref "R5") (pin "2") (pinfunction "2_2") (pintype "passive"))
      (node (ref "U3") (pin "15") (pinfunction "Q0_15") (pintype "passive"))
    )
    (net (code "15") (name "/Pin2") (class "Default")
      (node (ref "R6") (pin "2") (pinfunction "2_2") (pintype "passive"))
      (node (ref "U3") (pin "1") (pinfunction "Q1_1") (pintype "passive"))
    )
    (net (code "16") (name "/Pin3") (class "Default")
      (node (ref "R14") (pin "2") (pinfunction "2_2") (pintype "passive"))
      (node (ref "U3") (pin "2") (pinfunction "Q2_2") (pintype "passive"))
    )
    (net (code "17") (name "/Pin4") (class "Default")
      (node (ref "R15") (pin "2") (pinfunction "2_2") (pintype "passive"))
      (node (ref "U3") (pin "3") (pinfunction "Q3_3") (pintype "passive"))
    )
    (net (code "18") (name "/Pin5") (class "Default")
      (node (ref "R22") (pin "2") (pinfunction "2_2") (pintype "passive"))
      (node (ref "U3") (pin "4") (pinfunction "Q4_4") (pintype "passive"))
    )
    (net (code "19") (name "/Pin6") (class "Default")
      (node (ref "R23") (pin "2") (pinfunction "2_2") (pintype "passive"))
      (node (ref "U3") (pin "5") (pinfunction "Q5_5") (pintype "passive"))
    )
    (net (code "20") (name "/Pin7") (class "Default")
      (node (ref "R30") (pin "2") (pinfunction "2_2") (pintype "passive"))
      (node (ref "U3") (pin "6") (pinfunction "Q6_6") (pintype "passive"))
    )
    (net (code "21") (name "/Pin8") (class "Default")
      (node (ref "R31") (pin "2") (pinfunction "2_2") (pintype "passive"))
      (node (ref "U3") (pin "7") (pinfunction "Q7_7") (pintype "passive"))
    )
    (net (code "22") (name "/Pin9") (class "Default")
      (node (ref "R7") (pin "2") (pinfunction "2_2") (pintype "passive"))
      (node (ref "U4") (pin "15") (pinfunction "Q0_15") (pintype "passive"))
    )
    (net (code "23") (name "/Pin10") (class "Default")
      (node (ref "R16") (pin "2") (pinfunction "2_2") (pintype "passive"))
      (node (ref "U4") (pin "1") (pinfunction "Q1_1") (pintype "passive"))
    )
    (net (code "24") (name "/Pin11") (class "Default")
      (node (ref "R24") (pin "2") (pinfunction "2_2") (pintype "passive"))
      (node (ref "U4") (pin "2") (pinfunction "Q2_2") (pintype "passive"))
    )
    (net (code "25") (name "/Pin12") (class "Default")
      (node (ref "R32") (pin "2") (pinfunction "2_2") (pintype "passive"))
      (node (ref "U4") (pin "3") (pinfunction "Q3_3") (pintype "passive"))
    )
    (net (code "26") (name "/Pin13") (class "Default")
      (node (ref "R17") (pin "2") (pinfunction "2_2") (pintype "passive"))
      (node (ref "U4") (pin "4") (pinfunction "Q4_4") (pintype "passive"))
    )
    (net (code "27") (name "/Pin14") (class "Default")
      (node (ref "R25") (pin "2") (pinfunction "2_2") (pintype "passive"))
      (node (ref "U4") (pin "5") (pinfunction "Q5_5") (pintype "passive"))
    )
    (net (code "28") (name "/Pin15") (class "Default")
      (node (ref "R33") (pin "2") (pinfunction "2_2") (pintype "passive"))
      (node (ref "U4") (pin "6") (pinfunction "Q6_6") (pintype "passive"))
    )
    (net (code "29") (name "/Pulse_1") (class "Default")
      (node (ref "STM1") (pin "27") (pinfunction "A2_27") (pintype "passive"))
      (node (ref "U3") (pin "11") (pinfunction "SHCP_11") (pintype "passive"))
    )
    (net (code "30") (name "/Pulse_2") (class "Default")
      (node (ref "STM1") (pin "14") (pinfunction "B6_14") (pintype "passive"))
      (node (ref "U4") (pin "11") (pinfunction "SHCP_11") (pintype "passive"))
    )
    (net (code "31") (name "/USART1_RX") (class "Default")
      (node (ref "P2") (pin "2") (pinfunction "2_2") (pintype "passive"))
      (node (ref "STM1") (pin "7") (pinfunction "A10_7") (pintype "passive"))
    )
    (net (code "32") (name "/USART1_TX") (class "Default")
      (node (ref "P2") (pin "3") (pinfunction "3_3") (pintype "passive"))
      (node (ref "STM1") (pin "6") (pinfunction "A9_6") (pintype "passive"))
    )
    (net (code "33") (name "12V") (class "Default")
      (node (ref "C1") (pin "1") (pinfunction "1_1") (pintype "passive"))
      (node (ref "C2") (pin "1") (pinfunction "1_1") (pintype "passive"))
      (node (ref "LM1") (pin "1") (pinfunction "Vin_1") (pintype "passive"))
      (node (ref "P1") (pin "2") (pinfunction "2_2") (pintype "passive"))
    )
    (net (code "34") (name "GND") (class "Default")
      (node (ref "C1") (pin "2") (pinfunction "2_2") (pintype "passive"))
      (node (ref "C10") (pin "2") (pinfunction "2_2") (pintype "passive"))
      (node (ref "C11") (pin "2") (pinfunction "2_2") (pintype "passive"))
      (node (ref "C12") (pin "2") (pinfunction "2_2") (pintype "passive"))
      (node (ref "C13") (pin "2") (pinfunction "2_2") (pintype "passive"))
      (node (ref "C2") (pin "2") (pinfunction "2_2") (pintype "passive"))
      (node (ref "C3") (pin "2") (pinfunction "2_2") (pintype "passive"))
      (node (ref "C4") (pin "2") (pinfunction "2_2") (pintype "passive"))
      (node (ref "C5") (pin "2") (pinfunction "2_2") (pintype "passive"))
      (node (ref "C6") (pin "2") (pinfunction "2_2") (pintype "passive"))
      (node (ref "C7") (pin "2") (pinfunction "2_2") (pintype "passive"))
      (node (ref "C8") (pin "2") (pinfunction "2_2") (pintype "passive"))
      (node (ref "C9") (pin "2") (pinfunction "2_2") (pintype "passive"))
      (node (ref "D1") (pin "1") (pinfunction "A_1") (pintype "passive"))
      (node (ref "D10") (pin "2") (pinfunction "K_2") (pintype "passive"))
      (node (ref "D11") (pin "2") (pinfunction "K_2") (pintype "passive"))
      (node (ref "D12") (pin "2") (pinfunction "K_2") (pintype "passive"))
      (node (ref "D13") (pin "2") (pinfunction "K_2") (pintype "passive"))
      (node (ref "D14") (pin "2") (pinfunction "K_2") (pintype "passive"))
      (node (ref "D17") (pin "2") (pinfunction "K_2") (pintype "passive"))
      (node (ref "D18") (pin "2") (pinfunction "K_2") (pintype "passive"))
      (node (ref "D19") (pin "2") (pinfunction "K_2") (pintype "passive"))
      (node (ref "D20") (pin "2") (pinfunction "K_2") (pintype "passive"))
      (node (ref "D21") (pin "2") (pinfunction "K_2") (pintype "passive"))
      (node (ref "D22") (pin "2") (pinfunction "K_2") (pintype "passive"))
      (node (ref "D23") (pin "2") (pinfunction "K_2") (pintype "passive"))
      (node (ref "D24") (pin "2") (pinfunction "K_2") (pintype "passive"))
      (node (ref "D25") (pin "2") (pinfunction "K_2") (pintype "passive"))
      (node (ref "D26") (pin "2") (pinfunction "K_2") (pintype "passive"))
      (node (ref "D27") (pin "2") (pinfunction "K_2") (pintype "passive"))
      (node (ref "D28") (pin "2") (pinfunction "K_2") (pintype "passive"))
      (node (ref "D29") (pin "2") (pinfunction "K_2") (pintype "passive"))
      (node (ref "D30") (pin "2") (pinfunction "K_2") (pintype "passive"))
      (node (ref "D31") (pin "2") (pinfunction "K_2") (pintype "passive"))
      (node (ref "D32") (pin "2") (pinfunction "K_2") (pintype "passive"))
      (node (ref "D33") (pin "2") (pinfunction "K_2") (pintype "passive"))
      (node (ref "D34") (pin "2") (pinfunction "K_2") (pintype "passive"))
      (node (ref "D35") (pin "2") (pinfunction "K_2") (pintype "passive"))
      (node (ref "D36") (pin "2") (pinfunction "K_2") (pintype "passive"))
      (node (ref "D37") (pin "2") (pinfunction "K_2") (pintype "passive"))
      (node (ref "D38") (pin "2") (pinfunction "K_2") (pintype "passive"))
      (node (ref "D39") (pin "2") (pinfunction "K_2") (pintype "passive"))
      (node (ref "D4") (pin "2") (pinfunction "K_2") (pintype "passive"))
      (node (ref "D40") (pin "2") (pinfunction "K_2") (pintype "passive"))
      (node (ref "D41") (pin "2") (pinfunction "K_2") (pintype "passive"))
      (node (ref "D42") (pin "2") (pinfunction "K_2") (pintype "passive"))
      (node (ref "D43") (pin "2") (pinfunction "K_2") (pintype "passive"))
      (node (ref "D44") (pin "2") (pinfunction "K_2") (pintype "passive"))
      (node (ref "D45") (pin "2") (pinfunction "K_2") (pintype "passive"))
      (node (ref "D46") (pin "2") (pinfunction "K_2") (pintype "passive"))
      (node (ref "D47") (pin "2") (pinfunction "K_2") (pintype "passive"))
      (node (ref "D48") (pin "2") (pinfunction "K_2") (pintype "passive"))
      (node (ref "D49") (pin "2") (pinfunction "K_2") (pintype "passive"))
      (node (ref "D5") (pin "2") (pinfunction "K_2") (pintype "passive"))
      (node (ref "D50") (pin "2") (pinfunction "K_2") (pintype "passive"))
      (node (ref "D51") (pin "2") (pinfunction "K_2") (pintype "passive"))
      (node (ref "D52") (pin "2") (pinfunction "K_2") (pintype "passive"))
      (node (ref "D53") (pin "2") (pinfunction "K_2") (pintype "passive"))
      (node (ref "D54") (pin "2") (pinfunction "K_2") (pintype "passive"))
      (node (ref "D55") (pin "2") (pinfunction "K_2") (pintype "passive"))
      (node (ref "D56") (pin "2") (pinfunction "K_2") (pintype "passive"))
      (node (ref "D57") (pin "2") (pinfunction "K_2") (pintype "passive"))
      (node (ref "D58") (pin "2") (pinfunction "K_2") (pintype "passive"))
      (node (ref "D59") (pin "2") (pinfunction "K_2") (pintype "passive"))
      (node (ref "D6") (pin "2") (pinfunction "K_2") (pintype "passive"))
      (node (ref "D60") (pin "2") (pinfunction "K_2") (pintype "passive"))
      (node (ref "D61") (pin "2") (pinfunction "K_2") (pintype "passive"))
      (node (ref "D62") (pin "2") (pinfunction "K_2") (pintype "passive"))
      (node (ref "D63") (pin "2") (pinfunction "K_2") (pintype "passive"))
      (node (ref "D64") (pin "2") (pinfunction "K_2") (pintype "passive"))
      (node (ref "D65") (pin "2") (pinfunction "K_2") (pintype "passive"))
      (node (ref "D66") (pin "2") (pinfunction "K_2") (pintype "passive"))
      (node (ref "D67") (pin "2") (pinfunction "K_2") (pintype "passive"))
      (node (ref "D68") (pin "2") (pinfunction "K_2") (pintype "passive"))
      (node (ref "D69") (pin "2") (pinfunction "K_2") (pintype "passive"))
      (node (ref "D7") (pin "2") (pinfunction "K_2") (pintype "passive"))
      (node (ref "D70") (pin "2") (pinfunction "K_2") (pintype "passive"))
      (node (ref "D71") (pin "2") (pinfunction "K_2") (pintype "passive"))
      (node (ref "D72") (pin "2") (pinfunction "K_2") (pintype "passive"))
      (node (ref "D73") (pin "2") (pinfunction "K_2") (pintype "passive"))
      (node (ref "D74") (pin "2") (pinfunction "K_2") (pintype "passive"))
      (node (ref "D75") (pin "2") (pinfunction "K_2") (pintype "passive"))
      (node (ref "D76") (pin "2") (pinfunction "K_2") (pintype "passive"))
      (node (ref "D77") (pin "2") (pinfunction "K_2") (pintype "passive"))
      (node (ref "D78") (pin "2") (pinfunction "K_2") (pintype "passive"))
      (node (ref "D79") (pin "2") (pinfunction "K_2") (pintype "passive"))
      (node (ref "D8") (pin "2") (pinfunction "K_2") (pintype "passive"))
      (node (ref "D80") (pin "2") (pinfunction "K_2") (pintype "passive"))
      (node (ref "D81") (pin "2") (pinfunction "K_2") (pintype "passive"))
      (node (ref "D82") (pin "2") (pinfunction "K_2") (pintype "passive"))
      (node (ref "D9") (pin "2") (pinfunction "K_2") (pintype "passive"))
      (node (ref "LM1") (pin "3") (pinfunction "GND_3") (pintype "passive"))
      (node (ref "LM1") (pin "5") (pinfunction "~{ON}/OFF_5") (pintype "passive"))
      (node (ref "P1") (pin "1") (pinfunction "1_1") (pintype "passive"))
      (node (ref "P2") (pin "4") (pinfunction "4_4") (pintype "passive"))
      (node (ref "R1") (pin "1") (pinfunction "1_1") (pintype "passive"))
      (node (ref "STM1") (pin "19") (pinfunction "GND_19") (pintype "passive"))
      (node (ref "STM1") (pin "39") (pinfunction "GND_39") (pintype "passive"))
      (node (ref "STM1") (pin "40") (pinfunction "GND_40") (pintype "passive"))
      (node (ref "U1") (pin "1") (pinfunction "GND_1") (pintype "passive"))
      (node (ref "U2") (pin "1") (pinfunction "GND_1") (pintype "passive"))
      (node (ref "U3") (pin "8") (pinfunction "GND_8") (pintype "passive"))
      (node (ref "U4") (pin "8") (pinfunction "GND_8") (pintype "passive"))
    )
    (net (code "35") (name "Net-(D1-K)") (class "Default")
      (node (ref "D1") (pin "2") (pinfunction "K_2") (pintype "passive"))
      (node (ref "L1") (pin "1") (pinfunction "1_1") (pintype "passive"))
      (node (ref "LM1") (pin "2") (pinfunction "Output_2") (pintype "passive"))
    )
    (net (code "36") (name "Net-(D2-K)") (class "Default")
      (node (ref "D2") (pin "2") (pinfunction "K_2") (pintype "passive"))
      (node (ref "R1") (pin "2") (pinfunction "2_2") (pintype "passive"))
    )
    (net (code "37") (name "Net-(D3-A)") (class "Default")
      (node (ref "D3") (pin "1") (pinfunction "A_1") (pintype "passive"))
      (node (ref "R8") (pin "1") (pinfunction "1_1") (pintype "passive"))
    )
    (net (code "38") (name "Net-(D4-A)") (class "Default")
      (node (ref "D4") (pin "1") (pinfunction "A_1") (pintype "passive"))
      (node (ref "Q1") (pin "2") (pinfunction "E_2") (pintype "passive"))
    )
    (net (code "39") (name "Net-(D5-A)") (class "Default")
      (node (ref "D5") (pin "1") (pinfunction "A_1") (pintype "passive"))
      (node (ref "Q2") (pin "2") (pinfunction "E_2") (pintype "passive"))
    )
    (net (code "40") (name "Net-(D10-A)") (class "Default")
      (node (ref "D10") (pin "1") (pinfunction "A_1") (pintype "passive"))
      (node (ref "D11") (pin "1") (pinfunction "A_1") (pintype "passive"))
      (node (ref "D12") (pin "1") (pinfunction "A_1") (pintype "passive"))
      (node (ref "D13") (pin "1") (pinfunction "A_1") (pintype "passive"))
      (node (ref "D14") (pin "1") (pinfunction "A_1") (pintype "passive"))
      (node (ref "D6") (pin "1") (pinfunction "A_1") (pintype "passive"))
      (node (ref "D7") (pin "1") (pinfunction "A_1") (pintype "passive"))
      (node (ref "D8") (pin "1") (pinfunction "A_1") (pintype "passive"))
      (node (ref "D9") (pin "1") (pinfunction "A_1") (pintype "passive"))
      (node (ref "Q3") (pin "2") (pinfunction "E_2") (pintype "passive"))
    )
    (net (code "41") (name "Net-(D16-A)") (class "Default")
      (node (ref "D16") (pin "1") (pinfunction "A_1") (pintype "passive"))
      (node (ref "R9") (pin "1") (pinfunction "1_1") (pintype "passive"))
    )
    (net (code "42") (name "Net-(D17-A)") (class "Default")
      (node (ref "D17") (pin "1") (pinfunction "A_1") (pintype "passive"))
      (node (ref "Q4") (pin "2") (pinfunction "E_2") (pintype "passive"))
    )
    (net (code "43") (name "Net-(D18-A)") (class "Default")
      (node (ref "D18") (pin "1") (pinfunction "A_1") (pintype "passive"))
      (node (ref "Q5") (pin "2") (pinfunction "E_2") (pintype "passive"))
    )
    (net (code "44") (name "Net-(D19-A)") (class "Default")
      (node (ref "D19") (pin "1") (pinfunction "A_1") (pintype "passive"))
      (node (ref "D20") (pin "1") (pinfunction "A_1") (pintype "passive"))
      (node (ref "D21") (pin "1") (pinfunction "A_1") (pintype "passive"))
      (node (ref "D22") (pin "1") (pinfunction "A_1") (pintype "passive"))
      (node (ref "D23") (pin "1") (pinfunction "A_1") (pintype "passive"))
      (node (ref "D24") (pin "1") (pinfunction "A_1") (pintype "passive"))
      (node (ref "D25") (pin "1") (pinfunction "A_1") (pintype "passive"))
      (node (ref "D26") (pin "1") (pinfunction "A_1") (pintype "passive"))
      (node (ref "D27") (pin "1") (pinfunction "A_1") (pintype "passive"))
      (node (ref "D28") (pin "1") (pinfunction "A_1") (pintype "passive"))
      (node (ref "Q6") (pin "2") (pinfunction "E_2") (pintype "passive"))
    )
    (net (code "45") (name "Net-(D29-A)") (class "Default")
      (node (ref "D29") (pin "1") (pinfunction "A_1") (pintype "passive"))
      (node (ref "D30") (pin "1") (pinfunction "A_1") (pintype "passive"))
      (node (ref "D31") (pin "1") (pinfunction "A_1") (pintype "passive"))
      (node (ref "D32") (pin "1") (pinfunction "A_1") (pintype "passive"))
      (node (ref "D33") (pin "1") (pinfunction "A_1") (pintype "passive"))
      (node (ref "D34") (pin "1") (pinfunction "A_1") (pintype "passive"))
      (node (ref "D35") (pin "1") (pinfunction "A_1") (pintype "passive"))
      (node (ref "D36") (pin "1") (pinfunction "A_1") (pintype "passive"))
      (node (ref "D37") (pin "1") (pinfunction "A_1") (pintype "passive"))
      (node (ref "D38") (pin "1") (pinfunction "A_1") (pintype "passive"))
      (node (ref "Q7") (pin "2") (pinfunction "E_2") (pintype "passive"))
    )
    (net (code "46") (name "Net-(D39-A)") (class "Default")
      (node (ref "D39") (pin "1") (pinfunction "A_1") (pintype "passive"))
      (node (ref "Q8") (pin "2") (pinfunction "E_2") (pintype "passive"))
    )
    (net (code "47") (name "Net-(D40-A)") (class "Default")
      (node (ref "D40") (pin "1") (pinfunction "A_1") (pintype "passive"))
      (node (ref "Q9") (pin "2") (pinfunction "E_2") (pintype "passive"))
    )
    (net (code "48") (name "Net-(D41-A)") (class "Default")
      (node (ref "D41") (pin "1") (pinfunction "A_1") (pintype "passive"))
      (node (ref "D42") (pin "1") (pinfunction "A_1") (pintype "passive"))
      (node (ref "D43") (pin "1") (pinfunction "A_1") (pintype "passive"))
      (node (ref "D44") (pin "1") (pinfunction "A_1") (pintype "passive"))
      (node (ref "D45") (pin "1") (pinfunction "A_1") (pintype "passive"))
      (node (ref "D46") (pin "1") (pinfunction "A_1") (pintype "passive"))
      (node (ref "D47") (pin "1") (pinfunction "A_1") (pintype "passive"))
      (node (ref "D48") (pin "1") (pinfunction "A_1") (pintype "passive"))
      (node (ref "D49") (pin "1") (pinfunction "A_1") (pintype "passive"))
      (node (ref "D50") (pin "1") (pinfunction "A_1") (pintype "passive"))
      (node (ref "Q10") (pin "2") (pinfunction "E_2") (pintype "passive"))
    )
    (net (code "49") (name "Net-(D51-A)") (class "Default")
      (node (ref "D51") (pin "1") (pinfunction "A_1") (pintype "passive"))
      (node (ref "D52") (pin "1") (pinfunction "A_1") (pintype "passive"))
      (node (ref "D53") (pin "1") (pinfunction "A_1") (pintype "passive"))
      (node (ref "D54") (pin "1") (pinfunction "A_1") (pintype "passive"))
      (node (ref "D55") (pin "1") (pinfunction "A_1") (pintype "passive"))
      (node (ref "D56") (pin "1") (pinfunction "A_1") (pintype "passive"))
      (node (ref "D57") (pin "1") (pinfunction "A_1") (pintype "passive"))
      (node (ref "D58") (pin "1") (pinfunction "A_1") (pintype "passive"))
      (node (ref "D59") (pin "1") (pinfunction "A_1") (pintype "passive"))
      (node (ref "D60") (pin "1") (pinfunction "A_1") (pintype "passive"))
      (node (ref "Q11") (pin "2") (pinfunction "E_2") (pintype "passive"))
    )
    (net (code "50") (name "Net-(D61-A)") (class "Default")
      (node (ref "D61") (pin "1") (pinfunction "A_1") (pintype "passive"))
      (node (ref "Q12") (pin "2") (pinfunction "E_2") (pintype "passive"))
    )
    (net (code "51") (name "Net-(D62-A)") (class "Default")
      (node (ref "D62") (pin "1") (pinfunction "A_1") (pintype "passive"))
      (node (ref "Q13") (pin "2") (pinfunction "E_2") (pintype "passive"))
    )
    (net (code "52") (name "Net-(D63-A)") (class "Default")
      (node (ref "D63") (pin "1") (pinfunction "A_1") (pintype "passive"))
      (node (ref "D64") (pin "1") (pinfunction "A_1") (pintype "passive"))
      (node (ref "D65") (pin "1") (pinfunction "A_1") (pintype "passive"))
      (node (ref "D66") (pin "1") (pinfunction "A_1") (pintype "passive"))
      (node (ref "D67") (pin "1") (pinfunction "A_1") (pintype "passive"))
      (node (ref "D68") (pin "1") (pinfunction "A_1") (pintype "passive"))
      (node (ref "D69") (pin "1") (pinfunction "A_1") (pintype "passive"))
      (node (ref "D70") (pin "1") (pinfunction "A_1") (pintype "passive"))
      (node (ref "D71") (pin "1") (pinfunction "A_1") (pintype "passive"))
      (node (ref "D72") (pin "1") (pinfunction "A_1") (pintype "passive"))
      (node (ref "Q14") (pin "2") (pinfunction "E_2") (pintype "passive"))
    )
    (net (code "53") (name "Net-(D73-A)") (class "Default")
      (node (ref "D73") (pin "1") (pinfunction "A_1") (pintype "passive"))
      (node (ref "D74") (pin "1") (pinfunction "A_1") (pintype "passive"))
      (node (ref "D75") (pin "1") (pinfunction "A_1") (pintype "passive"))
      (node (ref "D76") (pin "1") (pinfunction "A_1") (pintype "passive"))
      (node (ref "D77") (pin "1") (pinfunction "A_1") (pintype "passive"))
      (node (ref "D78") (pin "1") (pinfunction "A_1") (pintype "passive"))
      (node (ref "D79") (pin "1") (pinfunction "A_1") (pintype "passive"))
      (node (ref "D80") (pin "1") (pinfunction "A_1") (pintype "passive"))
      (node (ref "D81") (pin "1") (pinfunction "A_1") (pintype "passive"))
      (node (ref "D82") (pin "1") (pinfunction "A_1") (pintype "passive"))
      (node (ref "Q15") (pin "2") (pinfunction "E_2") (pintype "passive"))
    )
    (net (code "54") (name "Net-(Q1-B)") (class "Default")
      (node (ref "Q1") (pin "1") (pinfunction "B_1") (pintype "passive"))
      (node (ref "R5") (pin "1") (pinfunction "1_1") (pintype "passive"))
    )
    (net (code "55") (name "Net-(Q1-C)") (class "Default")
      (node (ref "Q1") (pin "3") (pinfunction "C_3") (pintype "passive"))
      (node (ref "R2") (pin "2") (pinfunction "2_2") (pintype "passive"))
    )
    (net (code "56") (name "Net-(Q2-B)") (class "Default")
      (node (ref "Q2") (pin "1") (pinfunction "B_1") (pintype "passive"))
      (node (ref "R6") (pin "1") (pinfunction "1_1") (pintype "passive"))
    )
    (net (code "57") (name "Net-(Q2-C)") (class "Default")
      (node (ref "Q2") (pin "3") (pinfunction "C_3") (pintype "passive"))
      (node (ref "R3") (pin "2") (pinfunction "2_2") (pintype "passive"))
    )
    (net (code "58") (name "Net-(Q3-B)") (class "Default")
      (node (ref "Q3") (pin "1") (pinfunction "B_1") (pintype "passive"))
      (node (ref "R7") (pin "1") (pinfunction "1_1") (pintype "passive"))
    )
    (net (code "59") (name "Net-(Q3-C)") (class "Default")
      (node (ref "Q3") (pin "3") (pinfunction "C_3") (pintype "passive"))
      (node (ref "R4") (pin "2") (pinfunction "2_2") (pintype "passive"))
    )
    (net (code "60") (name "Net-(Q4-B)") (class "Default")
      (node (ref "Q4") (pin "1") (pinfunction "B_1") (pintype "passive"))
      (node (ref "R14") (pin "1") (pinfunction "1_1") (pintype "passive"))
    )
    (net (code "61") (name "Net-(Q4-C)") (class "Default")
      (node (ref "Q4") (pin "3") (pinfunction "C_3") (pintype "passive"))
      (node (ref "R10") (pin "2") (pinfunction "2_2") (pintype "passive"))
    )
    (net (code "62") (name "Net-(Q5-B)") (class "Default")
      (node (ref "Q5") (pin "1") (pinfunction "B_1") (pintype "passive"))
      (node (ref "R15") (pin "1") (pinfunction "1_1") (pintype "passive"))
    )
    (net (code "63") (name "Net-(Q5-C)") (class "Default")
      (node (ref "Q5") (pin "3") (pinfunction "C_3") (pintype "passive"))
      (node (ref "R11") (pin "2") (pinfunction "2_2") (pintype "passive"))
    )
    (net (code "64") (name "Net-(Q6-B)") (class "Default")
      (node (ref "Q6") (pin "1") (pinfunction "B_1") (pintype "passive"))
      (node (ref "R16") (pin "1") (pinfunction "1_1") (pintype "passive"))
    )
    (net (code "65") (name "Net-(Q6-C)") (class "Default")
      (node (ref "Q6") (pin "3") (pinfunction "C_3") (pintype "passive"))
      (node (ref "R12") (pin "2") (pinfunction "2_2") (pintype "passive"))
    )
    (net (code "66") (name "Net-(Q7-B)") (class "Default")
      (node (ref "Q7") (pin "1") (pinfunction "B_1") (pintype "passive"))
      (node (ref "R17") (pin "1") (pinfunction "1_1") (pintype "passive"))
    )
    (net (code "67") (name "Net-(Q7-C)") (class "Default")
      (node (ref "Q7") (pin "3") (pinfunction "C_3") (pintype "passive"))
      (node (ref "R13") (pin "2") (pinfunction "2_2") (pintype "passive"))
    )
    (net (code "68") (name "Net-(Q8-B)") (class "Default")
      (node (ref "Q8") (pin "1") (pinfunction "B_1") (pintype "passive"))
      (node (ref "R22") (pin "1") (pinfunction "1_1") (pintype "passive"))
    )
    (net (code "69") (name "Net-(Q8-C)") (class "Default")
      (node (ref "Q8") (pin "3") (pinfunction "C_3") (pintype "passive"))
      (node (ref "R18") (pin "2") (pinfunction "2_2") (pintype "passive"))
    )
    (net (code "70") (name "Net-(Q9-B)") (class "Default")
      (node (ref "Q9") (pin "1") (pinfunction "B_1") (pintype "passive"))
      (node (ref "R23") (pin "1") (pinfunction "1_1") (pintype "passive"))
    )
    (net (code "71") (name "Net-(Q9-C)") (class "Default")
      (node (ref "Q9") (pin "3") (pinfunction "C_3") (pintype "passive"))
      (node (ref "R19") (pin "2") (pinfunction "2_2") (pintype "passive"))
    )
    (net (code "72") (name "Net-(Q10-B)") (class "Default")
      (node (ref "Q10") (pin "1") (pinfunction "B_1") (pintype "passive"))
      (node (ref "R24") (pin "1") (pinfunction "1_1") (pintype "passive"))
    )
    (net (code "73") (name "Net-(Q10-C)") (class "Default")
      (node (ref "Q10") (pin "3") (pinfunction "C_3") (pintype "passive"))
      (node (ref "R20") (pin "2") (pinfunction "2_2") (pintype "passive"))
    )
    (net (code "74") (name "Net-(Q11-B)") (class "Default")
      (node (ref "Q11") (pin "1") (pinfunction "B_1") (pintype "passive"))
      (node (ref "R25") (pin "1") (pinfunction "1_1") (pintype "passive"))
    )
    (net (code "75") (name "Net-(Q11-C)") (class "Default")
      (node (ref "Q11") (pin "3") (pinfunction "C_3") (pintype "passive"))
      (node (ref "R21") (pin "2") (pinfunction "2_2") (pintype "passive"))
    )
    (net (code "76") (name "Net-(Q12-B)") (class "Default")
      (node (ref "Q12") (pin "1") (pinfunction "B_1") (pintype "passive"))
      (node (ref "R30") (pin "1") (pinfunction "1_1") (pintype "passive"))
    )
    (net (code "77") (name "Net-(Q12-C)") (class "Default")
      (node (ref "Q12") (pin "3") (pinfunction "C_3") (pintype "passive"))
      (node (ref "R26") (pin "2") (pinfunction "2_2") (pintype "passive"))
    )
    (net (code "78") (name "Net-(Q13-B)") (class "Default")
      (node (ref "Q13") (pin "1") (pinfunction "B_1") (pintype "passive"))
      (node (ref "R31") (pin "1") (pinfunction "1_1") (pintype "passive"))
    )
    (net (code "79") (name "Net-(Q13-C)") (class "Default")
      (node (ref "Q13") (pin "3") (pinfunction "C_3") (pintype "passive"))
      (node (ref "R27") (pin "2") (pinfunction "2_2") (pintype "passive"))
    )
    (net (code "80") (name "Net-(Q14-B)") (class "Default")
      (node (ref "Q14") (pin "1") (pinfunction "B_1") (pintype "passive"))
      (node (ref "R32") (pin "1") (pinfunction "1_1") (pintype "passive"))
    )
    (net (code "81") (name "Net-(Q14-C)") (class "Default")
      (node (ref "Q14") (pin "3") (pinfunction "C_3") (pintype "passive"))
      (node (ref "R28") (pin "2") (pinfunction "2_2") (pintype "passive"))
    )
    (net (code "82") (name "Net-(Q15-B)") (class "Default")
      (node (ref "Q15") (pin "1") (pinfunction "B_1") (pintype "passive"))
      (node (ref "R33") (pin "1") (pinfunction "1_1") (pintype "passive"))
    )
    (net (code "83") (name "Net-(Q15-C)") (class "Default")
      (node (ref "Q15") (pin "3") (pinfunction "C_3") (pintype "passive"))
      (node (ref "R29") (pin "2") (pinfunction "2_2") (pintype "passive"))
    )
    (net (code "84") (name "unconnected-(STM1-3.3V-Pad20)") (class "Default")
      (node (ref "STM1") (pin "20") (pinfunction "3.3V_20") (pintype "passive"))
    )
    (net (code "85") (name "unconnected-(STM1-5V-Pad18)") (class "Default")
      (node (ref "STM1") (pin "18") (pinfunction "5V_18") (pintype "passive"))
    )
    (net (code "86") (name "unconnected-(STM1-A0-Pad25)") (class "Default")
      (node (ref "STM1") (pin "25") (pinfunction "A0_25") (pintype "passive"))
    )
    (net (code "87") (name "unconnected-(STM1-A6-Pad31)") (class "Default")
      (node (ref "STM1") (pin "31") (pinfunction "A6_31") (pintype "passive"))
    )
    (net (code "88") (name "unconnected-(STM1-A7-Pad32)") (class "Default")
      (node (ref "STM1") (pin "32") (pinfunction "A7_32") (pintype "passive"))
    )
    (net (code "89") (name "unconnected-(STM1-A8-Pad5)") (class "Default")
      (node (ref "STM1") (pin "5") (pinfunction "A8_5") (pintype "passive"))
    )
    (net (code "90") (name "unconnected-(STM1-A11-Pad8)") (class "Default")
      (node (ref "STM1") (pin "8") (pinfunction "A11_8") (pintype "passive"))
    )
    (net (code "91") (name "unconnected-(STM1-A12-Pad9)") (class "Default")
      (node (ref "STM1") (pin "9") (pinfunction "A12_9") (pintype "passive"))
    )
    (net (code "92") (name "unconnected-(STM1-A15-Pad10)") (class "Default")
      (node (ref "STM1") (pin "10") (pinfunction "A15_10") (pintype "passive"))
    )
    (net (code "93") (name "unconnected-(STM1-B8-Pad16)") (class "Default")
      (node (ref "STM1") (pin "16") (pinfunction "B8_16") (pintype "passive"))
    )
    (net (code "94") (name "unconnected-(STM1-B9-Pad17)") (class "Default")
      (node (ref "STM1") (pin "17") (pinfunction "B9_17") (pintype "passive"))
    )
    (net (code "95") (name "unconnected-(STM1-B10-Pad35)") (class "Default")
      (node (ref "STM1") (pin "35") (pinfunction "B10_35") (pintype "passive"))
    )
    (net (code "96") (name "unconnected-(STM1-B11-Pad36)") (class "Default")
      (node (ref "STM1") (pin "36") (pinfunction "B11_36") (pintype "passive"))
    )
    (net (code "97") (name "unconnected-(STM1-B12-Pad1)") (class "Default")
      (node (ref "STM1") (pin "1") (pinfunction "B12_1") (pintype "passive"))
    )
    (net (code "98") (name "unconnected-(STM1-B13-Pad2)") (class "Default")
      (node (ref "STM1") (pin "2") (pinfunction "B13_2") (pintype "passive"))
    )
    (net (code "99") (name "unconnected-(STM1-B14-Pad3)") (class "Default")
      (node (ref "STM1") (pin "3") (pinfunction "B14_3") (pintype "passive"))
    )
    (net (code "100") (name "unconnected-(STM1-B15-Pad4)") (class "Default")
      (node (ref "STM1") (pin "4") (pinfunction "B15_4") (pintype "passive"))
    )
    (net (code "101") (name "unconnected-(STM1-C13-Pad22)") (class "Default")
      (node (ref "STM1") (pin "22") (pinfunction "C13_22") (pintype "passive"))
    )
    (net (code "102") (name "unconnected-(STM1-C14-Pad23)") (class "Default")
      (node (ref "STM1") (pin "23") (pinfunction "C14_23") (pintype "passive"))
    )
    (net (code "103") (name "unconnected-(STM1-C15-Pad24)") (class "Default")
      (node (ref "STM1") (pin "24") (pinfunction "C15_24") (pintype "passive"))
    )
    (net (code "104") (name "unconnected-(STM1-R-Pad37)") (class "Default")
      (node (ref "STM1") (pin "37") (pinfunction "R_37") (pintype "passive"))
    )
    (net (code "105") (name "unconnected-(STM1-VB-Pad21)") (class "Default")
      (node (ref "STM1") (pin "21") (pinfunction "VB_21") (pintype "passive"))
    )
    (net (code "106") (name "unconnected-(U1-gnd-Pad4)") (class "Default")
      (node (ref "U1") (pin "4") (pinfunction "gnd_4") (pintype "passive"))
    )
    (net (code "107") (name "unconnected-(U2-gnd-Pad4)") (class "Default")
      (node (ref "U2") (pin "4") (pinfunction "gnd_4") (pintype "passive"))
    )
    (net (code "108") (name "unconnected-(U3-~{Q7}-Pad9)") (class "Default")
      (node (ref "U3") (pin "9") (pinfunction "~{Q7}_9") (pintype "passive"))
    )
    (net (code "109") (name "unconnected-(U4-Q7-Pad7)") (class "Default")
      (node (ref "U4") (pin "7") (pinfunction "Q7_7") (pintype "passive"))
    )
    (net (code "110") (name "unconnected-(U4-~{Q7}-Pad9)") (class "Default")
      (node (ref "U4") (pin "9") (pinfunction "~{Q7}_9") (pintype "passive"))
    )
  )
)
